# MCU.net
KiCad netlist of a schematic drawn in Altium Designer
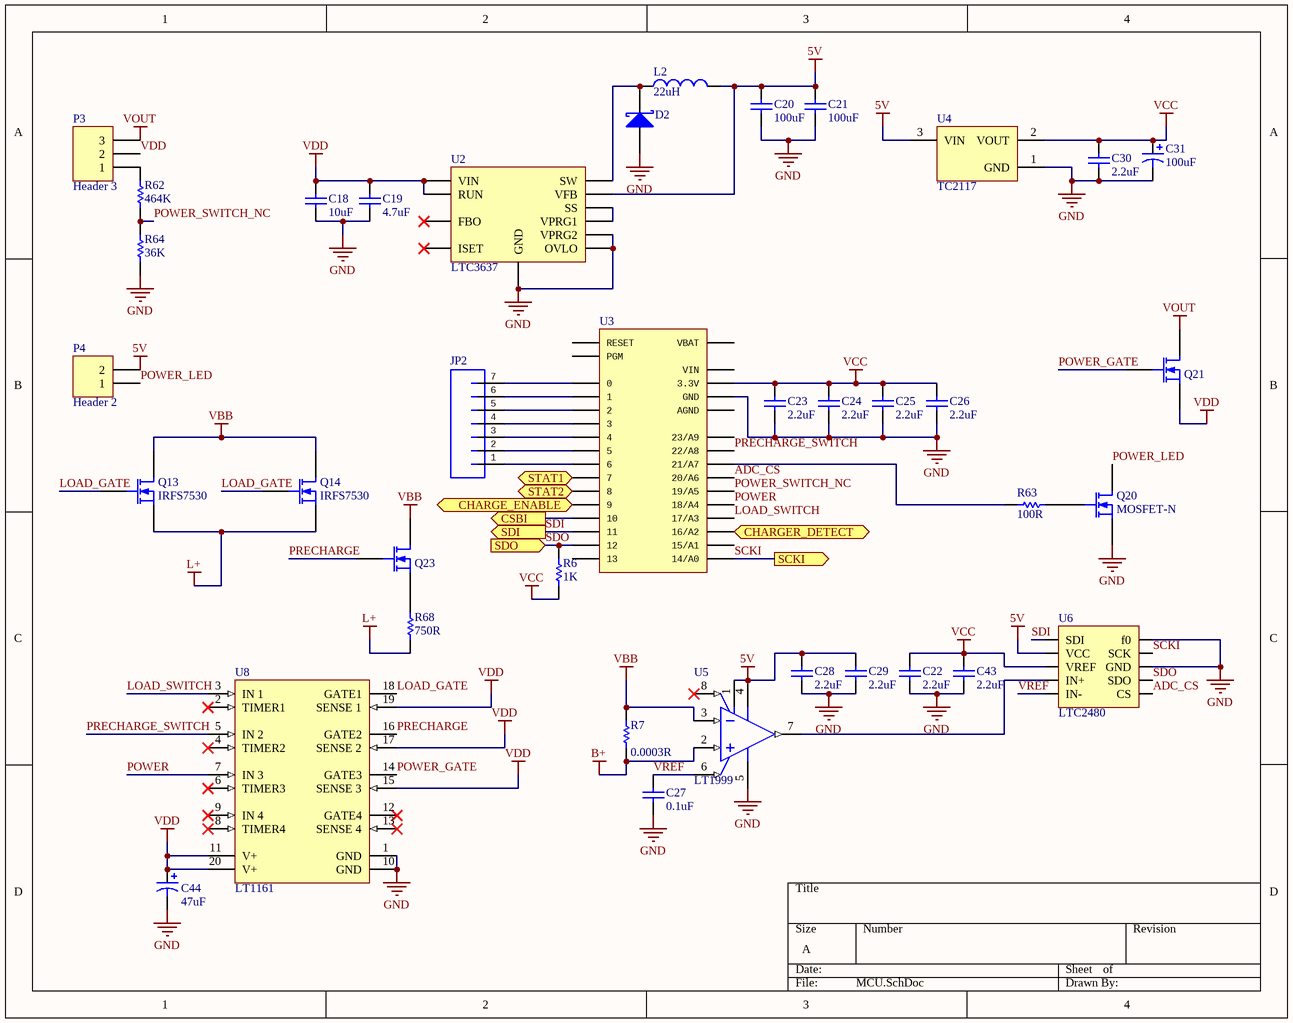
[diagram p0: MCU.SchDoc]

(export (version "E")
  (design (tool "Eeschema 10.0.6"))
  (components
    (comp (ref "C18")
      (value "10uF")
      (footprint "CAPC1206(3216)190_M")
      (description "CAP 10uF 50V Â±10% 1206 (3216 Metric) Thickness 1.9mm SMD")
      (fields (field (name "TOLERANCE") "Â±10%"))
      (libsource (lib "Altium Content Vault") (part "CMP-1037-04982-1"))
    )
    (comp (ref "C19")
      (value "4.7uF")
      (footprint "CAPC0805(2012)145_N")
      (description "CAP 4.7uF 50V Â±10% 0805 (2012 Metric) Thickness 1.45mm SMD")
      (fields (field (name "TOLERANCE") "Â±10%"))
      (libsource (lib "Altium Content Vault") (part "CMP-1036-04900-1"))
    )
    (comp (ref "C20")
      (value "100uF")
      (footprint "CAPC1210(3225)280_N")
      (description "CAP 100uF 10V Â±10% 1210 (3225 Metric) Thickness 2.8mm SMD")
      (fields (field (name "TOLERANCE") "Â±10%"))
      (libsource (lib "Altium Content Vault") (part "CMP-1038-02301-1"))
    )
    (comp (ref "C21")
      (value "100uF")
      (footprint "CAPC1210(3225)280_N")
      (description "CAP 100uF 10V Â±10% 1210 (3225 Metric) Thickness 2.8mm SMD")
      (fields (field (name "TOLERANCE") "Â±10%"))
      (libsource (lib "Altium Content Vault") (part "CMP-1038-02301-1"))
    )
    (comp (ref "C22")
      (value "2.2uF")
      (footprint "CAPC0603(1608)55_N")
      (description "CAP 2.2uF 4V Â±10% 0603 (1608 Metric) Thickness 0.55mm SMD")
      (fields (field (name "TOLERANCE") "Â±10%"))
      (libsource (lib "Altium Content Vault") (part "CMP-1035-02751-1"))
    )
    (comp (ref "C23")
      (value "2.2uF")
      (footprint "CAPC0603(1608)55_N")
      (description "CAP 2.2uF 16V Â±10% 0603 (1608 Metric) Thickness 0.55mm SMD")
      (fields (field (name "TOLERANCE") "Â±10%"))
      (libsource (lib "Altium Content Vault") (part "CMP-1035-02762-1"))
    )
    (comp (ref "C24")
      (value "2.2uF")
      (footprint "CAPC0603(1608)55_N")
      (description "CAP 2.2uF 16V Â±10% 0603 (1608 Metric) Thickness 0.55mm SMD")
      (fields (field (name "TOLERANCE") "Â±10%"))
      (libsource (lib "Altium Content Vault") (part "CMP-1035-02762-1"))
    )
    (comp (ref "C25")
      (value "2.2uF")
      (footprint "CAPC0603(1608)55_N")
      (description "CAP 2.2uF 16V Â±10% 0603 (1608 Metric) Thickness 0.55mm SMD")
      (fields (field (name "TOLERANCE") "Â±10%"))
      (libsource (lib "Altium Content Vault") (part "CMP-1035-02762-1"))
    )
    (comp (ref "C26")
      (value "2.2uF")
      (footprint "CAPC0603(1608)55_N")
      (description "CAP 2.2uF 16V Â±10% 0603 (1608 Metric) Thickness 0.55mm SMD")
      (fields (field (name "TOLERANCE") "Â±10%"))
      (libsource (lib "Altium Content Vault") (part "CMP-1035-02762-1"))
    )
    (comp (ref "C27")
      (value "0.1uF")
      (footprint "CAPC0603(1608)55_N")
      (description "CAP 2.2uF 16V Â±10% 0603 (1608 Metric) Thickness 0.55mm SMD")
      (fields (field (name "TOLERANCE") "Â±10%"))
      (libsource (lib "Altium Content Vault") (part "CMP-1035-02762-1"))
    )
    (comp (ref "C28")
      (value "2.2uF")
      (footprint "CAPC0603(1608)100_N")
      (description "CAP 100nF 6.3V Â±5% 0603 (1608 Metric) Thickness 1mm SMD")
      (fields (field (name "TOLERANCE") "Â±5%"))
      (libsource (lib "Altium Content Vault") (part "CMP-1035-02575-1"))
    )
    (comp (ref "C29")
      (value "2.2uF")
      (footprint "CAPC0603(1608)100_N")
      (description "CAP 1uF 6.3V Â±10% 0603 (1608 Metric) Thickness 1mm SMD")
      (fields (field (name "TOLERANCE") "Â±10%"))
      (libsource (lib "Altium Content Vault") (part "CMP-1035-02730-1"))
    )
    (comp (ref "C30")
      (value "2.2uF")
      (footprint "CAPC0603(1608)55_N")
      (description "CAP 2.2uF 16V Â±10% 0603 (1608 Metric) Thickness 0.55mm SMD")
      (fields (field (name "TOLERANCE") "Â±10%"))
      (libsource (lib "Altium Content Vault") (part "CMP-1035-02762-1"))
    )
    (comp (ref "C31")
      (value "100uF")
      (footprint "AVX-CAPC7343_V")
      (libsource (lib "Components") (part "AVX-CAP-P-2"))
    )
    (comp (ref "C43")
      (value "2.2uF")
      (footprint "CAPC0603(1608)55_N")
      (description "CAP 2.2uF 4V Â±10% 0603 (1608 Metric) Thickness 0.55mm SMD")
      (fields (field (name "TOLERANCE") "Â±10%"))
      (libsource (lib "Altium Content Vault") (part "CMP-1035-02751-1"))
    )
    (comp (ref "C44")
      (value "47uF")
      (footprint "CAP 300uF 6.3V")
      (description "Polarized Capacitor (Axial)")
      (fields (field (name "PUBLISHER") "Altium Limited"))
      (libsource (lib "Components") (part "CAP 47uF 50V"))
    )
    (comp (ref "D2")
      (value "~")
      (footprint "SMB")
      (description "Schottky Diode")
      (fields (field (name "PUBLISHER") "Altium Limited"))
      (libsource (lib "Miscellaneous Devices") (part "D Schottky"))
    )
    (comp (ref "JP2") (value "~") (footprint "JST-7-PTH") (libsource (lib "Components") (part "JST_7_RIGHT")))
    (comp (ref "L2")
      (value "22uH")
      (footprint "SDR0805-180ML")
      (description "Inductor")
      (fields (field (name "Comment") "SDR0805-180ML") (field (name "PUBLISHER") "Altium Limited"))
      (libsource (lib "Components") (part "SDR0805-180ML"))
    )
    (comp (ref "P3")
      (value "Header 3")
      (footprint "HDR1X3")
      (description "Header, 3-Pin")
      (fields (field (name "PUBLISHER") "Altium Limited"))
      (libsource (lib "Miscellaneous Connectors") (part "Header 3"))
    )
    (comp (ref "P4")
      (value "Header 2")
      (footprint "HDR1X2")
      (description "Header, 2-Pin")
      (fields (field (name "PUBLISHER") "Altium Limited"))
      (libsource (lib "Miscellaneous Connectors") (part "Header 2"))
    )
    (comp (ref "Q13")
      (value "IRFS7530")
      (footprint "DPAK127P1525X483-7N")
      (description "N-Channel MOSFET")
      (fields (field (name "PUBLISHER") "Altium Limited"))
      (libsource (lib "Components") (part "IRFS7530"))
    )
    (comp (ref "Q14")
      (value "IRFS7530")
      (footprint "DPAK127P1525X483-7N")
      (description "N-Channel MOSFET")
      (fields (field (name "PUBLISHER") "Altium Limited"))
      (libsource (lib "Components") (part "IRFS7530"))
    )
    (comp (ref "Q20")
      (value "MOSFET-N")
      (footprint "SOT23-3")
      (description "N-Channel MOSFET")
      (fields (field (name "PUBLISHER") "Altium Limited"))
      (libsource (lib "Components") (part "MOSFET-N"))
    )
    (comp (ref "Q21")
      (value "MOSFET-N")
      (footprint "SOIC127P600X175-8N")
      (description "N-Channel MOSFET")
      (fields (field (name "PUBLISHER") "Altium Limited"))
      (libsource (lib "Components") (part "MOSFET-N"))
    )
    (comp (ref "Q23")
      (value "MOSFET-N")
      (footprint "SOT23-3")
      (description "N-Channel MOSFET")
      (fields (field (name "PUBLISHER") "Altium Limited"))
      (libsource (lib "Components") (part "MOSFET-N"))
    )
    (comp (ref "R6")
      (value "1K")
      (footprint "RESC0603(1608)_L")
      (description "1K 0.1W 5% 0603 (1608 Metric)  SMD")
      (fields (field (name "TOLERANCE") "5 %") (field (name "POWER") "0.1 W"))
      (libsource (lib "Altium Content Vault") (part "RES"))
    )
    (comp (ref "R7")
      (value "0.0003R")
      (footprint "WSLP5931")
      (description "Resistor")
      (fields (field (name "PUBLISHER") "Altium Limited"))
      (libsource (lib "Components") (part "SHUNT"))
    )
    (comp (ref "R62")
      (value "464K")
      (footprint "RESC0603(1608)_M")
      (description "464K 0.1W 1% 0603 (1608 Metric)  SMD")
      (fields (field (name "TOLERANCE") "1 %") (field (name "POWER") "0.1 W"))
      (libsource (lib "Altium Content Vault") (part "RES"))
    )
    (comp (ref "R63")
      (value "100R")
      (footprint "RESC0603(1608)_L")
      (description "100R 0.1W 5% 0603 (1608 Metric)  SMD")
      (fields (field (name "TOLERANCE") "5 %") (field (name "POWER") "0.1 W"))
      (libsource (lib "Altium Content Vault") (part "RES"))
    )
    (comp (ref "R64")
      (value "36K")
      (footprint "RESC0603(1608)_M")
      (description "36K 0.1W 1% 0603 (1608 Metric)  SMD")
      (fields (field (name "POWER") "0.1 W") (field (name "TOLERANCE") "1 %"))
      (libsource (lib "Altium Content Vault") (part "RES"))
    )
    (comp (ref "R68")
      (value "750R")
      (footprint "RESC2512(6432)_N")
      (description "750R 1W 1% 2512 (6432 Metric)  SMD")
      (fields (field (name "TOLERANCE") "1 %") (field (name "POWER") "1 W"))
      (libsource (lib "Altium Content Vault") (part "RES"))
    )
    (comp (ref "U2")
      (value "LTC3637")
      (footprint "SON50P300X85_HS-17N")
      (libsource (lib "Components") (part "LTC3637"))
    )
    (comp (ref "U3")
      (value "~")
      (footprint "TEENSY_3.0_BASIC")
      (libsource (lib "Components") (part "TEENSY_3.0_BASIC"))
    )
    (comp (ref "U4")
      (value "TC2117")
      (footprint "SOT-223-DB3_M")
      (libsource (lib "Components") (part "PM-LINEREG-TC2117-IL4"))
    )
    (comp (ref "U5")
      (value "LT1999")
      (footprint "LT-MS8-8_N")
      (fields
        (field (name "MANUFACTURER") "Linear Technology")
        (field (name "PARTNUMBER") "LT1999HMS8-20#TRPBF")
        (field (name "LINEAR TECHNOLOGY PART NUMBER") "LT1999-20")
      )
      (libsource (lib "Altium Content Vault") (part "CMP-0359-00619-2"))
    )
    (comp (ref "U6") (value "LTC2480") (footprint "MSOP10") (libsource (lib "Components") (part "LTC2480")))
    (comp (ref "U8")
      (value "LT1161")
      (footprint "LT-SW-20_M")
      (fields (field (name "MANUFACTURER") "Linear Technology") (field (name "PARTNUMBER") "LT1161ISW#PBF"))
      (libsource (lib "Altium Inc") (part "LT-LT1161-20"))
    )
  )
  (nets
    (net (code "1") (name "/ADC_CS") (class "Default")
      (node (ref "U3") (pin "20/A6") (pinfunction "20/A6_20/A6") (pintype "passive"))
      (node (ref "U6") (pin "9") (pinfunction "CS_9") (pintype "passive"))
    )
    (net (code "2") (name "/CHARGER_DETECT") (class "Default")
      (node (ref "U3") (pin "16/A2") (pinfunction "16/A2_16/A2") (pintype "passive"))
    )
    (net (code "3") (name "/CHARGE_ENABLE") (class "Default")
      (node (ref "U3") (pin "9") (pinfunction "9_9") (pintype "passive"))
    )
    (net (code "4") (name "/CSBI") (class "Default")
      (node (ref "U3") (pin "10") (pinfunction "10_10") (pintype "passive"))
    )
    (net (code "5") (name "/LOAD_GATE") (class "Default")
      (node (ref "Q13") (pin "2") (pinfunction "G_2") (pintype "passive"))
      (node (ref "Q14") (pin "2") (pinfunction "G_2") (pintype "passive"))
      (node (ref "U8") (pin "18") (pinfunction "GATE1_18") (pintype "tri_state"))
    )
    (net (code "6") (name "/LOAD_SWITCH") (class "Default")
      (node (ref "U3") (pin "17/A3") (pinfunction "17/A3_17/A3") (pintype "passive"))
      (node (ref "U8") (pin "3") (pinfunction "IN_1_3") (pintype "input"))
    )
    (net (code "7") (name "/POWER") (class "Default")
      (node (ref "U3") (pin "18/A4") (pinfunction "18/A4_18/A4") (pintype "passive"))
      (node (ref "U8") (pin "7") (pinfunction "IN_3_7") (pintype "input"))
    )
    (net (code "8") (name "/POWER_GATE") (class "Default")
      (node (ref "Q21") (pin "1") (pinfunction "G_1") (pintype "passive"))
      (node (ref "U8") (pin "14") (pinfunction "GATE3_14") (pintype "tri_state"))
    )
    (net (code "9") (name "/POWER_LED") (class "Default")
      (node (ref "P4") (pin "1") (pinfunction "1_1") (pintype "passive"))
      (node (ref "Q20") (pin "2") (pinfunction "D_2") (pintype "passive"))
    )
    (net (code "10") (name "/POWER_SWITCH_NC") (class "Default")
      (node (ref "R62") (pin "1") (pinfunction "1_1") (pintype "passive"))
      (node (ref "R64") (pin "2") (pinfunction "2_2") (pintype "passive"))
      (node (ref "U3") (pin "19/A5") (pinfunction "19/A5_19/A5") (pintype "passive"))
    )
    (net (code "11") (name "/PRECHARGE") (class "Default")
      (node (ref "Q23") (pin "1") (pinfunction "G_1") (pintype "passive"))
      (node (ref "U8") (pin "16") (pinfunction "GATE2_16") (pintype "tri_state"))
    )
    (net (code "12") (name "/PRECHARGE_SWITCH") (class "Default")
      (node (ref "U3") (pin "22/A8") (pinfunction "22/A8_22/A8") (pintype "passive"))
      (node (ref "U8") (pin "5") (pinfunction "IN_2_5") (pintype "input"))
    )
    (net (code "13") (name "/SCKI") (class "Default")
      (node (ref "U3") (pin "14/A0") (pinfunction "14/A0_14/A0") (pintype "passive"))
      (node (ref "U6") (pin "6") (pinfunction "SCK_6") (pintype "passive"))
    )
    (net (code "14") (name "/SDI") (class "Default")
      (node (ref "U3") (pin "11") (pinfunction "11_11") (pintype "passive"))
      (node (ref "U6") (pin "0") (pinfunction "SDI_0") (pintype "passive"))
    )
    (net (code "15") (name "/SDO") (class "Default")
      (node (ref "R6") (pin "2") (pinfunction "2_2") (pintype "passive"))
      (node (ref "U3") (pin "12") (pinfunction "12_12") (pintype "passive"))
      (node (ref "U6") (pin "8") (pinfunction "SDO_8") (pintype "passive"))
    )
    (net (code "16") (name "/STAT1") (class "Default")
      (node (ref "U3") (pin "7") (pinfunction "7_7") (pintype "passive"))
    )
    (net (code "17") (name "/STAT2") (class "Default")
      (node (ref "U3") (pin "8") (pinfunction "8_8") (pintype "passive"))
    )
    (net (code "18") (name "/VREF") (class "Default")
      (node (ref "C27") (pin "2") (pinfunction "2_2") (pintype "passive"))
      (node (ref "U5") (pin "6") (pinfunction "REF_6") (pintype "input"))
      (node (ref "U6") (pin "4") (pinfunction "IN-_4") (pintype "passive"))
    )
    (net (code "19") (name "5V") (class "Default")
      (node (ref "C20") (pin "2") (pinfunction "2_2") (pintype "passive"))
      (node (ref "C21") (pin "2") (pinfunction "2_2") (pintype "passive"))
      (node (ref "C28") (pin "2") (pinfunction "2_2") (pintype "passive"))
      (node (ref "C29") (pin "2") (pinfunction "2_2") (pintype "passive"))
      (node (ref "L2") (pin "2") (pinfunction "2_2") (pintype "passive"))
      (node (ref "P4") (pin "2") (pinfunction "2_2") (pintype "passive"))
      (node (ref "U2") (pin "9") (pinfunction "VFB_9") (pintype "passive"))
      (node (ref "U4") (pin "3") (pinfunction "VIN_3") (pintype "power_in"))
      (node (ref "U5") (pin "1") (pinfunction "V+_1") (pintype "power_in"))
      (node (ref "U5") (pin "4") (pinfunction "V+_4") (pintype "power_in"))
      (node (ref "U6") (pin "1") (pinfunction "VCC_1") (pintype "passive"))
    )
    (net (code "20") (name "B+") (class "Default")
      (node (ref "R7") (pin "2") (pinfunction "2_2") (pintype "passive"))
      (node (ref "U5") (pin "2") (pinfunction "+IN_2") (pintype "input"))
    )
    (net (code "21") (name "GND") (class "Default")
      (node (ref "C18") (pin "1") (pinfunction "1_1") (pintype "passive"))
      (node (ref "C19") (pin "2") (pinfunction "2_2") (pintype "passive"))
      (node (ref "C20") (pin "1") (pinfunction "1_1") (pintype "passive"))
      (node (ref "C21") (pin "1") (pinfunction "1_1") (pintype "passive"))
      (node (ref "C22") (pin "1") (pinfunction "1_1") (pintype "passive"))
      (node (ref "C23") (pin "1") (pinfunction "1_1") (pintype "passive"))
      (node (ref "C24") (pin "1") (pinfunction "1_1") (pintype "passive"))
      (node (ref "C25") (pin "1") (pinfunction "1_1") (pintype "passive"))
      (node (ref "C26") (pin "1") (pinfunction "1_1") (pintype "passive"))
      (node (ref "C27") (pin "1") (pinfunction "1_1") (pintype "passive"))
      (node (ref "C28") (pin "1") (pinfunction "1_1") (pintype "passive"))
      (node (ref "C29") (pin "1") (pinfunction "1_1") (pintype "passive"))
      (node (ref "C30") (pin "2") (pinfunction "2_2") (pintype "passive"))
      (node (ref "C31") (pin "2") (pinfunction "2_2") (pintype "passive"))
      (node (ref "C43") (pin "1") (pinfunction "1_1") (pintype "passive"))
      (node (ref "C44") (pin "2") (pinfunction "2_2") (pintype "passive"))
      (node (ref "D2") (pin "1") (pinfunction "A_1") (pintype "passive"))
      (node (ref "Q20") (pin "3") (pinfunction "S_3") (pintype "passive"))
      (node (ref "R64") (pin "1") (pinfunction "1_1") (pintype "passive"))
      (node (ref "U2") (pin "12") (pinfunction "OVLO_12") (pintype "passive"))
      (node (ref "U2") (pin "17") (pinfunction "GND_17") (pintype "passive"))
      (node (ref "U2") (pin "6") (pinfunction "VPRG2_6") (pintype "passive"))
      (node (ref "U3") (pin "GND_GND1") (pinfunction "GND_GND_GND1") (pintype "power_in"))
      (node (ref "U4") (pin "1") (pinfunction "GND_1") (pintype "power_in"))
      (node (ref "U5") (pin "5") (pinfunction "GND_5") (pintype "power_in"))
      (node (ref "U6") (pin "5") (pinfunction "f0_5") (pintype "passive"))
      (node (ref "U6") (pin "7") (pinfunction "GND_7") (pintype "passive"))
      (node (ref "U8") (pin "1") (pinfunction "GND_1") (pintype "power_in"))
      (node (ref "U8") (pin "10") (pinfunction "GND_10") (pintype "power_in"))
    )
    (net (code "22") (name "L+") (class "Default")
      (node (ref "Q13") (pin "3") (pinfunction "S_3") (pintype "passive"))
      (node (ref "Q14") (pin "3") (pinfunction "S_3") (pintype "passive"))
      (node (ref "R68") (pin "1") (pinfunction "1_1") (pintype "passive"))
    )
    (net (code "23") (name "Net-(D2-K)") (class "Default")
      (node (ref "D2") (pin "2") (pinfunction "K_2") (pintype "passive"))
      (node (ref "L2") (pin "1") (pinfunction "1_1") (pintype "passive"))
      (node (ref "U2") (pin "1") (pinfunction "SW_1") (pintype "passive"))
    )
    (net (code "24") (name "Net-(JP2-Pad1)") (class "Default")
      (node (ref "JP2") (pin "1") (pinfunction "1_1") (pintype "passive"))
      (node (ref "U3") (pin "6") (pinfunction "6_6") (pintype "passive"))
    )
    (net (code "25") (name "Net-(JP2-Pad2)") (class "Default")
      (node (ref "JP2") (pin "2") (pinfunction "2_2") (pintype "passive"))
      (node (ref "U3") (pin "5") (pinfunction "5_5") (pintype "passive"))
    )
    (net (code "26") (name "Net-(JP2-Pad3)") (class "Default")
      (node (ref "JP2") (pin "3") (pinfunction "3_3") (pintype "passive"))
      (node (ref "U3") (pin "4") (pinfunction "4_4") (pintype "passive"))
    )
    (net (code "27") (name "Net-(JP2-Pad4)") (class "Default")
      (node (ref "JP2") (pin "4") (pinfunction "4_4") (pintype "passive"))
      (node (ref "U3") (pin "3") (pinfunction "3_3") (pintype "passive"))
    )
    (net (code "28") (name "Net-(JP2-Pad5)") (class "Default")
      (node (ref "JP2") (pin "5") (pinfunction "5_5") (pintype "passive"))
      (node (ref "U3") (pin "2") (pinfunction "2_2") (pintype "passive"))
    )
    (net (code "29") (name "Net-(JP2-Pad6)") (class "Default")
      (node (ref "JP2") (pin "6") (pinfunction "6_6") (pintype "passive"))
      (node (ref "U3") (pin "1") (pinfunction "1_1") (pintype "passive"))
    )
    (net (code "30") (name "Net-(JP2-Pad7)") (class "Default")
      (node (ref "JP2") (pin "7") (pinfunction "7_7") (pintype "passive"))
      (node (ref "U3") (pin "0") (pinfunction "0_0") (pintype "passive"))
    )
    (net (code "31") (name "Net-(P3-Pad1)") (class "Default")
      (node (ref "P3") (pin "1") (pinfunction "1_1") (pintype "passive"))
      (node (ref "R62") (pin "2") (pinfunction "2_2") (pintype "passive"))
    )
    (net (code "32") (name "Net-(Q20-G)") (class "Default")
      (node (ref "Q20") (pin "1") (pinfunction "G_1") (pintype "passive"))
      (node (ref "R63") (pin "2") (pinfunction "2_2") (pintype "passive"))
    )
    (net (code "33") (name "Net-(Q23-S)") (class "Default")
      (node (ref "Q23") (pin "3") (pinfunction "S_3") (pintype "passive"))
      (node (ref "R68") (pin "2") (pinfunction "2_2") (pintype "passive"))
    )
    (net (code "34") (name "Net-(R63-Pad1)") (class "Default")
      (node (ref "R63") (pin "1") (pinfunction "1_1") (pintype "passive"))
      (node (ref "U3") (pin "21/A7") (pinfunction "21/A7_21/A7") (pintype "passive"))
    )
    (net (code "35") (name "Net-(U2-SS)") (class "Default")
      (node (ref "U2") (pin "10") (pinfunction "SS_10") (pintype "passive"))
      (node (ref "U2") (pin "7") (pinfunction "VPRG1_7") (pintype "passive"))
    )
    (net (code "36") (name "Net-(U5-OUT)") (class "Default")
      (node (ref "U5") (pin "7") (pinfunction "OUT_7") (pintype "output"))
      (node (ref "U6") (pin "3") (pinfunction "IN+_3") (pintype "passive"))
    )
    (net (code "37") (name "VBB") (class "Default")
      (node (ref "Q13") (pin "1") (pinfunction "D_1") (pintype "passive"))
      (node (ref "Q14") (pin "1") (pinfunction "D_1") (pintype "passive"))
      (node (ref "Q23") (pin "2") (pinfunction "D_2") (pintype "passive"))
      (node (ref "R7") (pin "1") (pinfunction "1_1") (pintype "passive"))
      (node (ref "U5") (pin "3") (pinfunction "-IN_3") (pintype "input"))
    )
    (net (code "38") (name "VCC") (class "Default")
      (node (ref "C22") (pin "2") (pinfunction "2_2") (pintype "passive"))
      (node (ref "C23") (pin "2") (pinfunction "2_2") (pintype "passive"))
      (node (ref "C24") (pin "2") (pinfunction "2_2") (pintype "passive"))
      (node (ref "C25") (pin "2") (pinfunction "2_2") (pintype "passive"))
      (node (ref "C26") (pin "2") (pinfunction "2_2") (pintype "passive"))
      (node (ref "C30") (pin "1") (pinfunction "1_1") (pintype "passive"))
      (node (ref "C31") (pin "1") (pinfunction "1_1") (pintype "passive"))
      (node (ref "C43") (pin "2") (pinfunction "2_2") (pintype "passive"))
      (node (ref "R6") (pin "1") (pinfunction "1_1") (pintype "passive"))
      (node (ref "U3") (pin "3.3V_3.3V1") (pinfunction "3.3V_3.3V_3.3V1") (pintype "power_in"))
      (node (ref "U4") (pin "2") (pinfunction "VOUT_2") (pintype "power_in"))
      (node (ref "U6") (pin "2") (pinfunction "VREF_2") (pintype "passive"))
    )
    (net (code "39") (name "VDD") (class "Default")
      (node (ref "C18") (pin "2") (pinfunction "2_2") (pintype "passive"))
      (node (ref "C19") (pin "1") (pinfunction "1_1") (pintype "passive"))
      (node (ref "C44") (pin "1") (pinfunction "1_1") (pintype "passive"))
      (node (ref "P3") (pin "2") (pinfunction "2_2") (pintype "passive"))
      (node (ref "Q21") (pin "3") (pinfunction "S_3") (pintype "passive"))
      (node (ref "U2") (pin "14") (pinfunction "RUN_14") (pintype "passive"))
      (node (ref "U2") (pin "3") (pinfunction "VIN_3") (pintype "passive"))
      (node (ref "U8") (pin "11") (pinfunction "V+_11") (pintype "power_in"))
      (node (ref "U8") (pin "15") (pinfunction "SENSE_3_15") (pintype "input"))
      (node (ref "U8") (pin "17") (pinfunction "SENSE_2_17") (pintype "input"))
      (node (ref "U8") (pin "19") (pinfunction "SENSE_1_19") (pintype "input"))
      (node (ref "U8") (pin "20") (pinfunction "V+_20") (pintype "power_in"))
    )
    (net (code "40") (name "VOUT") (class "Default")
      (node (ref "P3") (pin "3") (pinfunction "3_3") (pintype "passive"))
      (node (ref "Q21") (pin "2") (pinfunction "D_2") (pintype "passive"))
    )
    (net (code "41") (name "unconnected-(U2-FBO-Pad5)") (class "Default")
      (node (ref "U2") (pin "5") (pinfunction "FBO_5") (pintype "passive+no_connect"))
    )
    (net (code "42") (name "unconnected-(U2-ISET-Pad11)") (class "Default")
      (node (ref "U2") (pin "11") (pinfunction "ISET_11") (pintype "passive+no_connect"))
    )
    (net (code "43") (name "unconnected-(U3-Pad13)") (class "Default")
      (node (ref "U3") (pin "13") (pinfunction "13_13") (pintype "passive"))
    )
    (net (code "44") (name "unconnected-(U3-Pad15{slash}A1)") (class "Default")
      (node (ref "U3") (pin "15/A1") (pinfunction "15/A1_15/A1") (pintype "passive"))
    )
    (net (code "45") (name "unconnected-(U3-Pad23{slash}A9)") (class "Default")
      (node (ref "U3") (pin "23/A9") (pinfunction "23/A9_23/A9") (pintype "passive"))
    )
    (net (code "46") (name "unconnected-(U3-PadAGND)") (class "Default")
      (node (ref "U3") (pin "AGND") (pinfunction "AGND_AGND") (pintype "power_in"))
    )
    (net (code "47") (name "unconnected-(U3-PadPGM)") (class "Default")
      (node (ref "U3") (pin "PGM") (pinfunction "PGM_PGM") (pintype "passive"))
    )
    (net (code "48") (name "unconnected-(U3-PadRESET)") (class "Default")
      (node (ref "U3") (pin "RESET") (pinfunction "RESET_RESET") (pintype "passive"))
    )
    (net (code "49") (name "unconnected-(U3-PadVBAT)") (class "Default")
      (node (ref "U3") (pin "VBAT") (pinfunction "VBAT_VBAT") (pintype "power_in"))
    )
    (net (code "50") (name "unconnected-(U3-PadVIN)") (class "Default")
      (node (ref "U3") (pin "VIN") (pinfunction "VIN_VIN") (pintype "power_in"))
    )
    (net (code "51") (name "unconnected-(U5-~{SHDN}-Pad8)") (class "Default")
      (node (ref "U5") (pin "8") (pinfunction "~{SHDN}_8") (pintype "input+no_connect"))
    )
    (net (code "52") (name "unconnected-(U8-GATE4-Pad12)") (class "Default")
      (node (ref "U8") (pin "12") (pinfunction "GATE4_12") (pintype "tri_state+no_connect"))
    )
    (net (code "53") (name "unconnected-(U8-IN_4-Pad9)") (class "Default")
      (node (ref "U8") (pin "9") (pinfunction "IN_4_9") (pintype "input+no_connect"))
    )
    (net (code "54") (name "unconnected-(U8-SENSE_4-Pad13)") (class "Default")
      (node (ref "U8") (pin "13") (pinfunction "SENSE_4_13") (pintype "input+no_connect"))
    )
    (net (code "55") (name "unconnected-(U8-TIMER1-Pad2)") (class "Default")
      (node (ref "U8") (pin "2") (pinfunction "TIMER1_2") (pintype "input+no_connect"))
    )
    (net (code "56") (name "unconnected-(U8-TIMER2-Pad4)") (class "Default")
      (node (ref "U8") (pin "4") (pinfunction "TIMER2_4") (pintype "input+no_connect"))
    )
    (net (code "57") (name "unconnected-(U8-TIMER3-Pad6)") (class "Default")
      (node (ref "U8") (pin "6") (pinfunction "TIMER3_6") (pintype "input+no_connect"))
    )
    (net (code "58") (name "unconnected-(U8-TIMER4-Pad8)") (class "Default")
      (node (ref "U8") (pin "8") (pinfunction "TIMER4_8") (pintype "input+no_connect"))
    )
  )
)
